# main.net
KiCad netlist of a schematic drawn in EAGLE
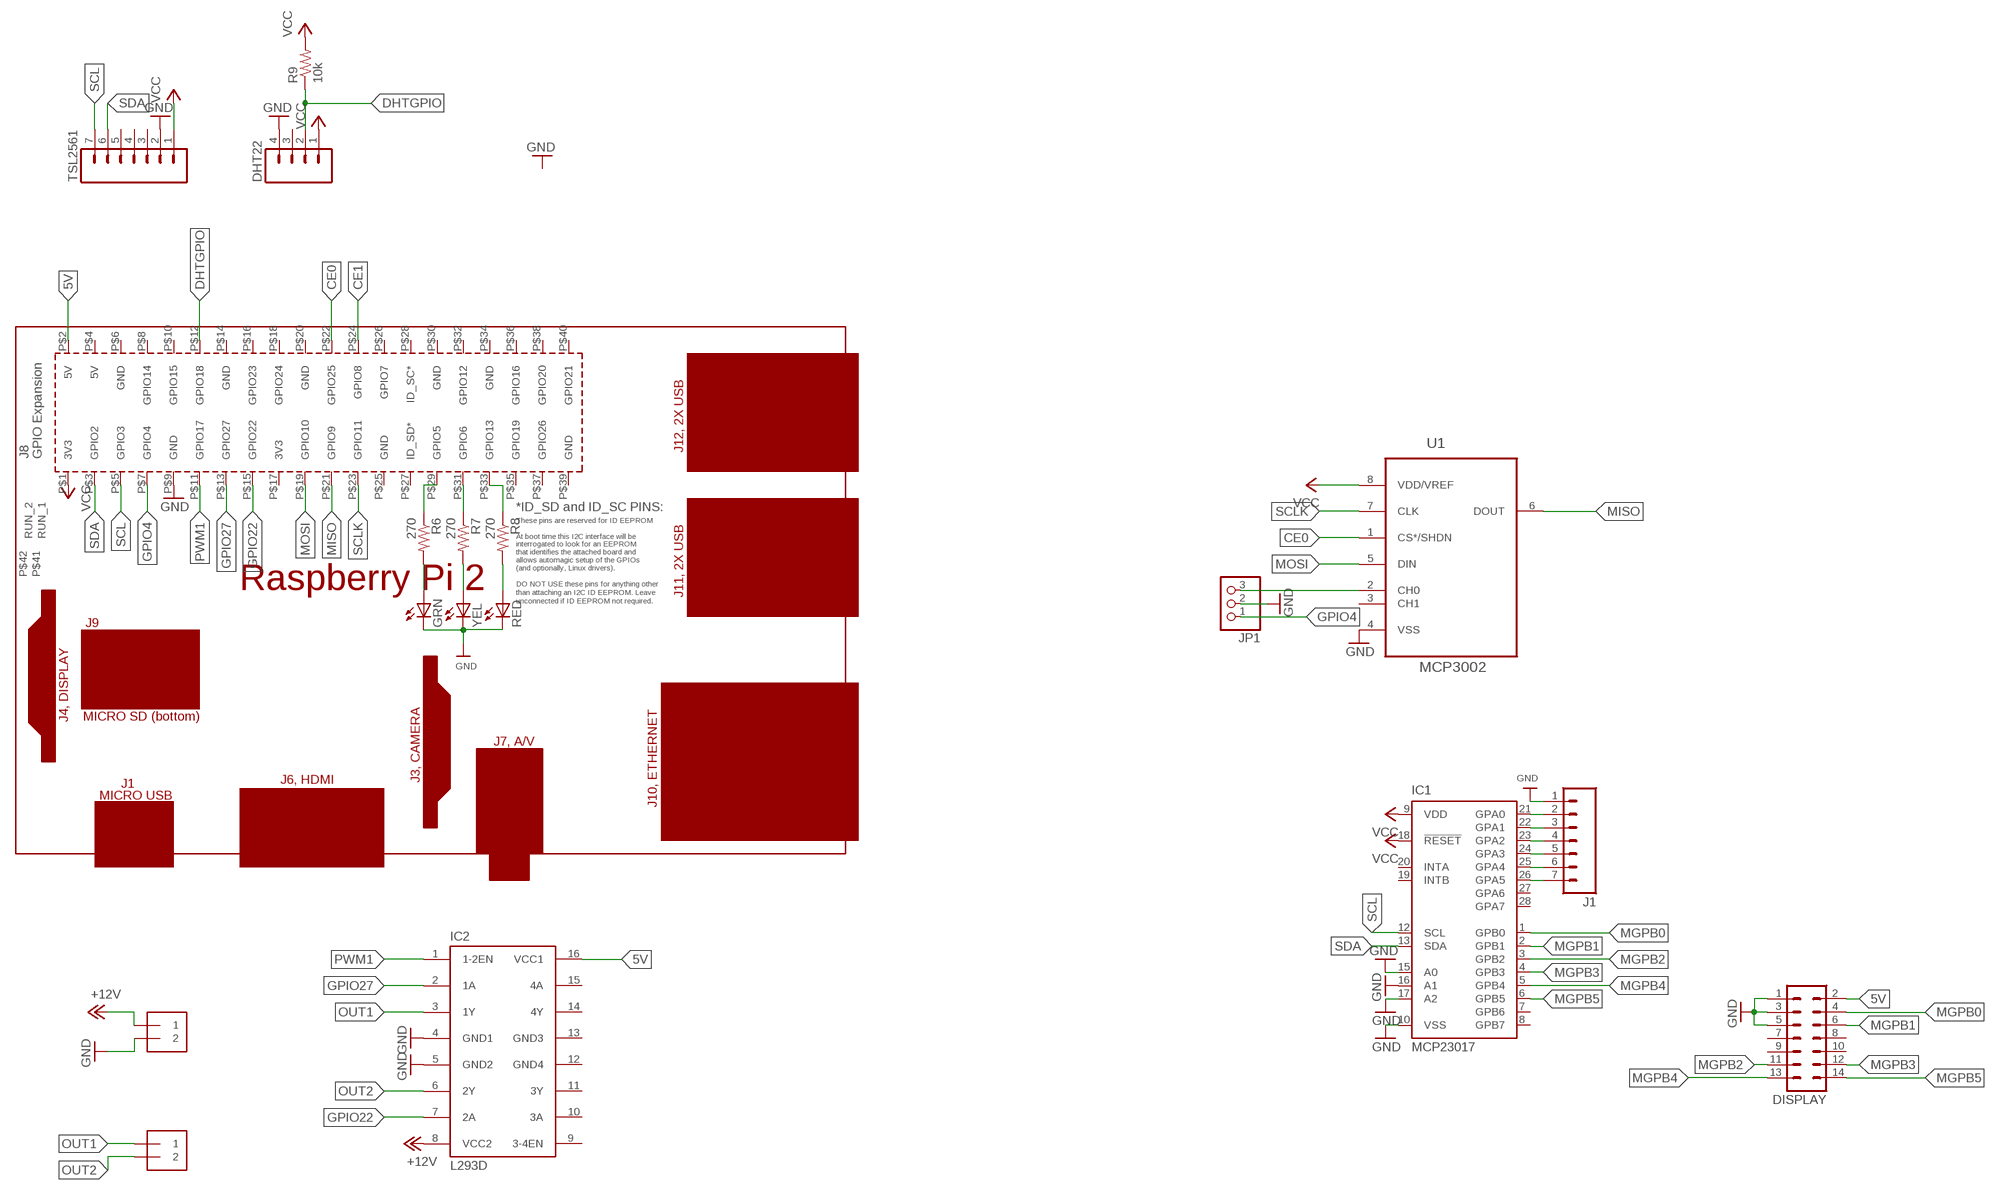
[diagram p0: schematic, sheet 1]

(export (version "E")
  (design (tool "Eeschema 10.0.6"))
  (components
    (comp (ref "DHT22")
      (value "M041X04_NO_SILK")
      (footprint "eagle-import:1X04_NO_SILK")
      (libsource (lib "eagle-import") (part "M041X04_NO_SILK"))
    )
    (comp (ref "DISPLAY")
      (value "MA07-2")
      (footprint "eagle-import:MA07-2")
      (libsource (lib "eagle-import") (part "MA07-2"))
    )
    (comp (ref "GRN")
      (value "LED3MM")
      (footprint "eagle-import:LED3MM")
      (libsource (lib "eagle-import") (part "LED3MM"))
    )
    (comp (ref "IC1")
      (value "MCP23017")
      (footprint "eagle-import:DIL28-3-ROUND")
      (libsource (lib "eagle-import") (part "MCP23017SP2"))
    )
    (comp (ref "IC2")
      (value "L293D")
      (footprint "eagle-import:DIL16")
      (libsource (lib "eagle-import") (part "L293D"))
    )
    (comp (ref "J1")
      (value "M07")
      (footprint "eagle-import:1X07")
      (libsource (lib "eagle-import") (part "M07"))
    )
    (comp (ref "J2")
      (value "1X2-3.5MM")
      (footprint "eagle-import:1X2-3.5MM")
      (libsource (lib "eagle-import") (part "1X2-3.5MM"))
    )
    (comp (ref "J3")
      (value "1X2-3.5MM")
      (footprint "eagle-import:1X2-3.5MM")
      (libsource (lib "eagle-import") (part "1X2-3.5MM"))
    )
    (comp (ref "JP1")
      (value "PINHD-1X3")
      (footprint "eagle-import:1X03")
      (libsource (lib "eagle-import") (part "PINHD-1X3"))
    )
    (comp (ref "PCB1")
      (value "RPI2")
      (footprint "eagle-import:RPI2")
      (libsource (lib "eagle-import") (part "RPI2"))
    )
    (comp (ref "R6")
      (value "270")
      (footprint "eagle-import:0204_7")
      (libsource (lib "eagle-import") (part "R-US_0204/7"))
    )
    (comp (ref "R7")
      (value "270")
      (footprint "eagle-import:0204_7")
      (libsource (lib "eagle-import") (part "R-US_0204/7"))
    )
    (comp (ref "R8")
      (value "270")
      (footprint "eagle-import:0204_7")
      (libsource (lib "eagle-import") (part "R-US_0204/7"))
    )
    (comp (ref "R9")
      (value "10k")
      (footprint "eagle-import:0204_7")
      (libsource (lib "eagle-import") (part "R-US_0204/7"))
    )
    (comp (ref "RED")
      (value "LED3MM")
      (footprint "eagle-import:LED3MM")
      (libsource (lib "eagle-import") (part "LED3MM"))
    )
    (comp (ref "TSL2561")
      (value "M07NO_SILK")
      (footprint "eagle-import:1X07_NO_SILK")
      (libsource (lib "eagle-import") (part "M07NO_SILK"))
    )
    (comp (ref "U1")
      (value "MCP3002")
      (footprint "eagle-import:DIP254P762X533-8")
      (fields (field (name "MPN") "MCP3002-I/P"))
      (libsource (lib "eagle-import") (part "MCP3002-I/P"))
    )
    (comp (ref "YEL")
      (value "LED3MM")
      (footprint "eagle-import:LED3MM")
      (libsource (lib "eagle-import") (part "LED3MM"))
    )
  )
  (nets
    (net (code "1") (name "+12V") (class "Default")
      (node (ref "IC2") (pin "8") (pinfunction "VCC2_8") (pintype "power_in"))
      (node (ref "J2") (pin "1") (pinfunction "1_1") (pintype "passive"))
    )
    (net (code "2") (name "/GND3") (class "Default")
      (node (ref "IC2") (pin "13") (pinfunction "GND3_13") (pintype "power_in"))
    )
    (net (code "3") (name "/GND4") (class "Default")
      (node (ref "IC2") (pin "12") (pinfunction "GND4_12") (pintype "power_in"))
    )
    (net (code "4") (name "5V") (class "Default")
      (node (ref "DISPLAY") (pin "2") (pinfunction "2_2") (pintype "passive"))
      (node (ref "IC2") (pin "16") (pinfunction "VCC1_16") (pintype "power_in"))
      (node (ref "PCB1") (pin "P$2") (pinfunction "5V_P$2") (pintype "bidirectional"))
    )
    (net (code "5") (name "CE0") (class "Default")
      (node (ref "PCB1") (pin "P$22") (pinfunction "GPIO25_P$22") (pintype "bidirectional"))
      (node (ref "U1") (pin "1") (pinfunction "CS*/SHDN_1") (pintype "input"))
    )
    (net (code "6") (name "CE1") (class "Default")
      (node (ref "PCB1") (pin "P$24") (pinfunction "GPIO8_P$24") (pintype "bidirectional"))
    )
    (net (code "7") (name "DHTGPIO") (class "Default")
      (node (ref "DHT22") (pin "2") (pinfunction "2_2") (pintype "passive"))
      (node (ref "PCB1") (pin "P$12") (pinfunction "GPIO18_P$12") (pintype "bidirectional"))
      (node (ref "R9") (pin "1") (pinfunction "1_1") (pintype "passive"))
    )
    (net (code "8") (name "GND") (class "Default")
      (node (ref "DHT22") (pin "4") (pinfunction "4_4") (pintype "passive"))
      (node (ref "DISPLAY") (pin "1") (pinfunction "1_1") (pintype "passive"))
      (node (ref "DISPLAY") (pin "3") (pinfunction "3_3") (pintype "passive"))
      (node (ref "DISPLAY") (pin "5") (pinfunction "5_5") (pintype "passive"))
      (node (ref "GRN") (pin "K") (pinfunction "C_K") (pintype "passive"))
      (node (ref "IC1") (pin "10") (pinfunction "VSS_10") (pintype "power_in"))
      (node (ref "IC1") (pin "15") (pinfunction "A0_15") (pintype "input"))
      (node (ref "IC1") (pin "16") (pinfunction "A1_16") (pintype "input"))
      (node (ref "IC1") (pin "17") (pinfunction "A2_17") (pintype "input"))
      (node (ref "IC2") (pin "4") (pinfunction "GND1_4") (pintype "power_in"))
      (node (ref "IC2") (pin "5") (pinfunction "GND2_5") (pintype "power_in"))
      (node (ref "J1") (pin "1") (pinfunction "1_1") (pintype "passive"))
      (node (ref "J2") (pin "2") (pinfunction "2_2") (pintype "passive"))
      (node (ref "JP1") (pin "2") (pinfunction "2_2") (pintype "passive"))
      (node (ref "PCB1") (pin "P$9") (pinfunction "GND_P$9") (pintype "bidirectional"))
      (node (ref "RED") (pin "K") (pinfunction "C_K") (pintype "passive"))
      (node (ref "TSL2561") (pin "2") (pinfunction "2_2") (pintype "passive"))
      (node (ref "U1") (pin "4") (pinfunction "VSS_4") (pintype "passive"))
      (node (ref "YEL") (pin "K") (pinfunction "C_K") (pintype "passive"))
    )
    (net (code "9") (name "GPIO4") (class "Default")
      (node (ref "JP1") (pin "1") (pinfunction "1_1") (pintype "passive"))
      (node (ref "PCB1") (pin "P$7") (pinfunction "GPIO4_P$7") (pintype "bidirectional"))
    )
    (net (code "10") (name "GPIO22") (class "Default")
      (node (ref "IC2") (pin "7") (pinfunction "2A_7") (pintype "input"))
      (node (ref "PCB1") (pin "P$15") (pinfunction "GPIO22_P$15") (pintype "bidirectional"))
    )
    (net (code "11") (name "GPIO27") (class "Default")
      (node (ref "IC2") (pin "2") (pinfunction "1A_2") (pintype "input"))
      (node (ref "PCB1") (pin "P$13") (pinfunction "GPIO27_P$13") (pintype "bidirectional"))
    )
    (net (code "12") (name "MGPB0") (class "Default")
      (node (ref "DISPLAY") (pin "4") (pinfunction "4_4") (pintype "passive"))
      (node (ref "IC1") (pin "1") (pinfunction "GPB0_1") (pintype "bidirectional"))
    )
    (net (code "13") (name "MGPB1") (class "Default")
      (node (ref "DISPLAY") (pin "6") (pinfunction "6_6") (pintype "passive"))
      (node (ref "IC1") (pin "2") (pinfunction "GPB1_2") (pintype "bidirectional"))
    )
    (net (code "14") (name "MGPB2") (class "Default")
      (node (ref "DISPLAY") (pin "11") (pinfunction "11_11") (pintype "passive"))
      (node (ref "IC1") (pin "3") (pinfunction "GPB2_3") (pintype "bidirectional"))
    )
    (net (code "15") (name "MGPB3") (class "Default")
      (node (ref "DISPLAY") (pin "12") (pinfunction "12_12") (pintype "passive"))
      (node (ref "IC1") (pin "4") (pinfunction "GPB3_4") (pintype "bidirectional"))
    )
    (net (code "16") (name "MGPB4") (class "Default")
      (node (ref "DISPLAY") (pin "13") (pinfunction "13_13") (pintype "passive"))
      (node (ref "IC1") (pin "5") (pinfunction "GPB4_5") (pintype "bidirectional"))
    )
    (net (code "17") (name "MGPB5") (class "Default")
      (node (ref "DISPLAY") (pin "14") (pinfunction "14_14") (pintype "passive"))
      (node (ref "IC1") (pin "6") (pinfunction "GPB5_6") (pintype "bidirectional"))
    )
    (net (code "18") (name "MISO") (class "Default")
      (node (ref "PCB1") (pin "P$21") (pinfunction "GPIO9_P$21") (pintype "bidirectional"))
      (node (ref "U1") (pin "6") (pinfunction "DOUT_6") (pintype "output"))
    )
    (net (code "19") (name "MOSI") (class "Default")
      (node (ref "PCB1") (pin "P$19") (pinfunction "GPIO10_P$19") (pintype "bidirectional"))
      (node (ref "U1") (pin "5") (pinfunction "DIN_5") (pintype "input"))
    )
    (net (code "20") (name "Net-(GRN-PadA)") (class "Default")
      (node (ref "GRN") (pin "A") (pinfunction "A_A") (pintype "passive"))
      (node (ref "R6") (pin "2") (pinfunction "2_2") (pintype "passive"))
    )
    (net (code "21") (name "Net-(IC1-GPA0)") (class "Default")
      (node (ref "IC1") (pin "21") (pinfunction "GPA0_21") (pintype "bidirectional"))
      (node (ref "J1") (pin "2") (pinfunction "2_2") (pintype "passive"))
    )
    (net (code "22") (name "Net-(IC1-GPA1)") (class "Default")
      (node (ref "IC1") (pin "22") (pinfunction "GPA1_22") (pintype "bidirectional"))
      (node (ref "J1") (pin "3") (pinfunction "3_3") (pintype "passive"))
    )
    (net (code "23") (name "Net-(IC1-GPA2)") (class "Default")
      (node (ref "IC1") (pin "23") (pinfunction "GPA2_23") (pintype "bidirectional"))
      (node (ref "J1") (pin "4") (pinfunction "4_4") (pintype "passive"))
    )
    (net (code "24") (name "Net-(IC1-GPA3)") (class "Default")
      (node (ref "IC1") (pin "24") (pinfunction "GPA3_24") (pintype "bidirectional"))
      (node (ref "J1") (pin "5") (pinfunction "5_5") (pintype "passive"))
    )
    (net (code "25") (name "Net-(IC1-GPA4)") (class "Default")
      (node (ref "IC1") (pin "25") (pinfunction "GPA4_25") (pintype "bidirectional"))
      (node (ref "J1") (pin "6") (pinfunction "6_6") (pintype "passive"))
    )
    (net (code "26") (name "Net-(IC1-GPA5)") (class "Default")
      (node (ref "IC1") (pin "26") (pinfunction "GPA5_26") (pintype "bidirectional"))
      (node (ref "J1") (pin "7") (pinfunction "7_7") (pintype "passive"))
    )
    (net (code "27") (name "Net-(PCB1-GPIO5)") (class "Default")
      (node (ref "PCB1") (pin "P$29") (pinfunction "GPIO5_P$29") (pintype "bidirectional"))
      (node (ref "R6") (pin "1") (pinfunction "1_1") (pintype "passive"))
    )
    (net (code "28") (name "Net-(PCB1-GPIO6)") (class "Default")
      (node (ref "PCB1") (pin "P$31") (pinfunction "GPIO6_P$31") (pintype "bidirectional"))
      (node (ref "R7") (pin "1") (pinfunction "1_1") (pintype "passive"))
    )
    (net (code "29") (name "Net-(PCB1-GPIO13)") (class "Default")
      (node (ref "PCB1") (pin "P$33") (pinfunction "GPIO13_P$33") (pintype "bidirectional"))
      (node (ref "R8") (pin "1") (pinfunction "1_1") (pintype "passive"))
    )
    (net (code "30") (name "Net-(R7-Pad2)") (class "Default")
      (node (ref "R7") (pin "2") (pinfunction "2_2") (pintype "passive"))
      (node (ref "YEL") (pin "A") (pinfunction "A_A") (pintype "passive"))
    )
    (net (code "31") (name "Net-(R8-Pad2)") (class "Default")
      (node (ref "R8") (pin "2") (pinfunction "2_2") (pintype "passive"))
      (node (ref "RED") (pin "A") (pinfunction "A_A") (pintype "passive"))
    )
    (net (code "32") (name "Net-(U1-CH0)") (class "Default")
      (node (ref "JP1") (pin "3") (pinfunction "3_3") (pintype "passive"))
      (node (ref "U1") (pin "2") (pinfunction "CH0_2") (pintype "input"))
    )
    (net (code "33") (name "OUT1") (class "Default")
      (node (ref "IC2") (pin "3") (pinfunction "1Y_3") (pintype "output"))
      (node (ref "J3") (pin "1") (pinfunction "1_1") (pintype "passive"))
    )
    (net (code "34") (name "OUT2") (class "Default")
      (node (ref "IC2") (pin "6") (pinfunction "2Y_6") (pintype "output"))
      (node (ref "J3") (pin "2") (pinfunction "2_2") (pintype "passive"))
    )
    (net (code "35") (name "PWM1") (class "Default")
      (node (ref "IC2") (pin "1") (pinfunction "1-2EN_1") (pintype "input"))
      (node (ref "PCB1") (pin "P$11") (pinfunction "GPIO17_P$11") (pintype "bidirectional"))
    )
    (net (code "36") (name "SCL") (class "Default")
      (node (ref "IC1") (pin "12") (pinfunction "SCL_12") (pintype "input"))
      (node (ref "PCB1") (pin "P$5") (pinfunction "GPIO3_P$5") (pintype "bidirectional"))
      (node (ref "TSL2561") (pin "7") (pinfunction "7_7") (pintype "passive"))
    )
    (net (code "37") (name "SCLK") (class "Default")
      (node (ref "PCB1") (pin "P$23") (pinfunction "GPIO11_P$23") (pintype "bidirectional"))
      (node (ref "U1") (pin "7") (pinfunction "CLK_7") (pintype "input"))
    )
    (net (code "38") (name "SDA") (class "Default")
      (node (ref "IC1") (pin "13") (pinfunction "SDA_13") (pintype "bidirectional"))
      (node (ref "PCB1") (pin "P$3") (pinfunction "GPIO2_P$3") (pintype "bidirectional"))
      (node (ref "TSL2561") (pin "6") (pinfunction "6_6") (pintype "passive"))
    )
    (net (code "39") (name "VCC") (class "Default")
      (node (ref "DHT22") (pin "1") (pinfunction "1_1") (pintype "passive"))
      (node (ref "IC1") (pin "18") (pinfunction "~{RESET}_18") (pintype "input"))
      (node (ref "IC1") (pin "9") (pinfunction "VDD_9") (pintype "power_in"))
      (node (ref "PCB1") (pin "P$1") (pinfunction "3V3_P$1") (pintype "bidirectional"))
      (node (ref "R9") (pin "2") (pinfunction "2_2") (pintype "passive"))
      (node (ref "TSL2561") (pin "1") (pinfunction "1_1") (pintype "passive"))
      (node (ref "U1") (pin "8") (pinfunction "VDD/VREF_8") (pintype "power_in"))
    )
    (net (code "40") (name "unconnected-(DHT22-Pad3)") (class "Default")
      (node (ref "DHT22") (pin "3") (pinfunction "3_3") (pintype "passive"))
    )
    (net (code "41") (name "unconnected-(DISPLAY-Pad7)") (class "Default")
      (node (ref "DISPLAY") (pin "7") (pinfunction "7_7") (pintype "passive"))
    )
    (net (code "42") (name "unconnected-(DISPLAY-Pad8)") (class "Default")
      (node (ref "DISPLAY") (pin "8") (pinfunction "8_8") (pintype "passive"))
    )
    (net (code "43") (name "unconnected-(DISPLAY-Pad9)") (class "Default")
      (node (ref "DISPLAY") (pin "9") (pinfunction "9_9") (pintype "passive"))
    )
    (net (code "44") (name "unconnected-(DISPLAY-Pad10)") (class "Default")
      (node (ref "DISPLAY") (pin "10") (pinfunction "10_10") (pintype "passive"))
    )
    (net (code "45") (name "unconnected-(IC1-GPA6-Pad27)") (class "Default")
      (node (ref "IC1") (pin "27") (pinfunction "GPA6_27") (pintype "bidirectional"))
    )
    (net (code "46") (name "unconnected-(IC1-GPA7-Pad28)") (class "Default")
      (node (ref "IC1") (pin "28") (pinfunction "GPA7_28") (pintype "bidirectional"))
    )
    (net (code "47") (name "unconnected-(IC1-GPB6-Pad7)") (class "Default")
      (node (ref "IC1") (pin "7") (pinfunction "GPB6_7") (pintype "bidirectional"))
    )
    (net (code "48") (name "unconnected-(IC1-GPB7-Pad8)") (class "Default")
      (node (ref "IC1") (pin "8") (pinfunction "GPB7_8") (pintype "bidirectional"))
    )
    (net (code "49") (name "unconnected-(IC1-INTA-Pad20)") (class "Default")
      (node (ref "IC1") (pin "20") (pinfunction "INTA_20") (pintype "output"))
    )
    (net (code "50") (name "unconnected-(IC1-INTB-Pad19)") (class "Default")
      (node (ref "IC1") (pin "19") (pinfunction "INTB_19") (pintype "output"))
    )
    (net (code "51") (name "unconnected-(IC2-3-4EN-Pad9)") (class "Default")
      (node (ref "IC2") (pin "9") (pinfunction "3-4EN_9") (pintype "input"))
    )
    (net (code "52") (name "unconnected-(IC2-3A-Pad10)") (class "Default")
      (node (ref "IC2") (pin "10") (pinfunction "3A_10") (pintype "input"))
    )
    (net (code "53") (name "unconnected-(IC2-3Y-Pad11)") (class "Default")
      (node (ref "IC2") (pin "11") (pinfunction "3Y_11") (pintype "output"))
    )
    (net (code "54") (name "unconnected-(IC2-4A-Pad15)") (class "Default")
      (node (ref "IC2") (pin "15") (pinfunction "4A_15") (pintype "input"))
    )
    (net (code "55") (name "unconnected-(IC2-4Y-Pad14)") (class "Default")
      (node (ref "IC2") (pin "14") (pinfunction "4Y_14") (pintype "output"))
    )
    (net (code "56") (name "unconnected-(PCB1-3V3-PadP$17)") (class "Default")
      (node (ref "PCB1") (pin "P$17") (pinfunction "3V3_P$17") (pintype "bidirectional"))
    )
    (net (code "57") (name "unconnected-(PCB1-5V-PadP$4)") (class "Default")
      (node (ref "PCB1") (pin "P$4") (pinfunction "5V_P$4") (pintype "bidirectional"))
    )
    (net (code "58") (name "unconnected-(PCB1-GND-PadP$6)") (class "Default")
      (node (ref "PCB1") (pin "P$6") (pinfunction "GND_P$6") (pintype "bidirectional"))
    )
    (net (code "59") (name "unconnected-(PCB1-GND-PadP$14)") (class "Default")
      (node (ref "PCB1") (pin "P$14") (pinfunction "GND_P$14") (pintype "bidirectional"))
    )
    (net (code "60") (name "unconnected-(PCB1-GND-PadP$20)") (class "Default")
      (node (ref "PCB1") (pin "P$20") (pinfunction "GND_P$20") (pintype "bidirectional"))
    )
    (net (code "61") (name "unconnected-(PCB1-GND-PadP$25)") (class "Default")
      (node (ref "PCB1") (pin "P$25") (pinfunction "GND_P$25") (pintype "bidirectional"))
    )
    (net (code "62") (name "unconnected-(PCB1-GND-PadP$30)") (class "Default")
      (node (ref "PCB1") (pin "P$30") (pinfunction "GND_P$30") (pintype "bidirectional"))
    )
    (net (code "63") (name "unconnected-(PCB1-GND-PadP$34)") (class "Default")
      (node (ref "PCB1") (pin "P$34") (pinfunction "GND_P$34") (pintype "bidirectional"))
    )
    (net (code "64") (name "unconnected-(PCB1-GND-PadP$39)") (class "Default")
      (node (ref "PCB1") (pin "P$39") (pinfunction "GND_P$39") (pintype "bidirectional"))
    )
    (net (code "65") (name "unconnected-(PCB1-GPIO7-PadP$26)") (class "Default")
      (node (ref "PCB1") (pin "P$26") (pinfunction "GPIO7_P$26") (pintype "bidirectional"))
    )
    (net (code "66") (name "unconnected-(PCB1-GPIO12-PadP$32)") (class "Default")
      (node (ref "PCB1") (pin "P$32") (pinfunction "GPIO12_P$32") (pintype "bidirectional"))
    )
    (net (code "67") (name "unconnected-(PCB1-GPIO14-PadP$8)") (class "Default")
      (node (ref "PCB1") (pin "P$8") (pinfunction "GPIO14_P$8") (pintype "bidirectional"))
    )
    (net (code "68") (name "unconnected-(PCB1-GPIO15-PadP$10)") (class "Default")
      (node (ref "PCB1") (pin "P$10") (pinfunction "GPIO15_P$10") (pintype "bidirectional"))
    )
    (net (code "69") (name "unconnected-(PCB1-GPIO16-PadP$36)") (class "Default")
      (node (ref "PCB1") (pin "P$36") (pinfunction "GPIO16_P$36") (pintype "bidirectional"))
    )
    (net (code "70") (name "unconnected-(PCB1-GPIO19-PadP$35)") (class "Default")
      (node (ref "PCB1") (pin "P$35") (pinfunction "GPIO19_P$35") (pintype "bidirectional"))
    )
    (net (code "71") (name "unconnected-(PCB1-GPIO20-PadP$38)") (class "Default")
      (node (ref "PCB1") (pin "P$38") (pinfunction "GPIO20_P$38") (pintype "bidirectional"))
    )
    (net (code "72") (name "unconnected-(PCB1-GPIO21-PadP$40)") (class "Default")
      (node (ref "PCB1") (pin "P$40") (pinfunction "GPIO21_P$40") (pintype "bidirectional"))
    )
    (net (code "73") (name "unconnected-(PCB1-GPIO23-PadP$16)") (class "Default")
      (node (ref "PCB1") (pin "P$16") (pinfunction "GPIO23_P$16") (pintype "bidirectional"))
    )
    (net (code "74") (name "unconnected-(PCB1-GPIO24-PadP$18)") (class "Default")
      (node (ref "PCB1") (pin "P$18") (pinfunction "GPIO24_P$18") (pintype "bidirectional"))
    )
    (net (code "75") (name "unconnected-(PCB1-GPIO26-PadP$37)") (class "Default")
      (node (ref "PCB1") (pin "P$37") (pinfunction "GPIO26_P$37") (pintype "bidirectional"))
    )
    (net (code "76") (name "unconnected-(PCB1-ID_SC*-PadP$28)") (class "Default")
      (node (ref "PCB1") (pin "P$28") (pinfunction "ID_SC*_P$28") (pintype "bidirectional"))
    )
    (net (code "77") (name "unconnected-(PCB1-ID_SD*-PadP$27)") (class "Default")
      (node (ref "PCB1") (pin "P$27") (pinfunction "ID_SD*_P$27") (pintype "bidirectional"))
    )
    (net (code "78") (name "unconnected-(PCB1-RUN_1-PadP$41)") (class "Default")
      (node (ref "PCB1") (pin "P$41") (pinfunction "RUN_1_P$41") (pintype "bidirectional"))
    )
    (net (code "79") (name "unconnected-(PCB1-RUN_2-PadP$42)") (class "Default")
      (node (ref "PCB1") (pin "P$42") (pinfunction "RUN_2_P$42") (pintype "bidirectional"))
    )
    (net (code "80") (name "unconnected-(TSL2561-Pad3)") (class "Default")
      (node (ref "TSL2561") (pin "3") (pinfunction "3_3") (pintype "passive"))
    )
    (net (code "81") (name "unconnected-(TSL2561-Pad4)") (class "Default")
      (node (ref "TSL2561") (pin "4") (pinfunction "4_4") (pintype "passive"))
    )
    (net (code "82") (name "unconnected-(TSL2561-Pad5)") (class "Default")
      (node (ref "TSL2561") (pin "5") (pinfunction "5_5") (pintype "passive"))
    )
    (net (code "83") (name "unconnected-(U1-CH1-Pad3)") (class "Default")
      (node (ref "U1") (pin "3") (pinfunction "CH1_3") (pintype "input"))
    )
  )
)
